# GPIO_shield.net
KiCad netlist of a schematic drawn in EAGLE
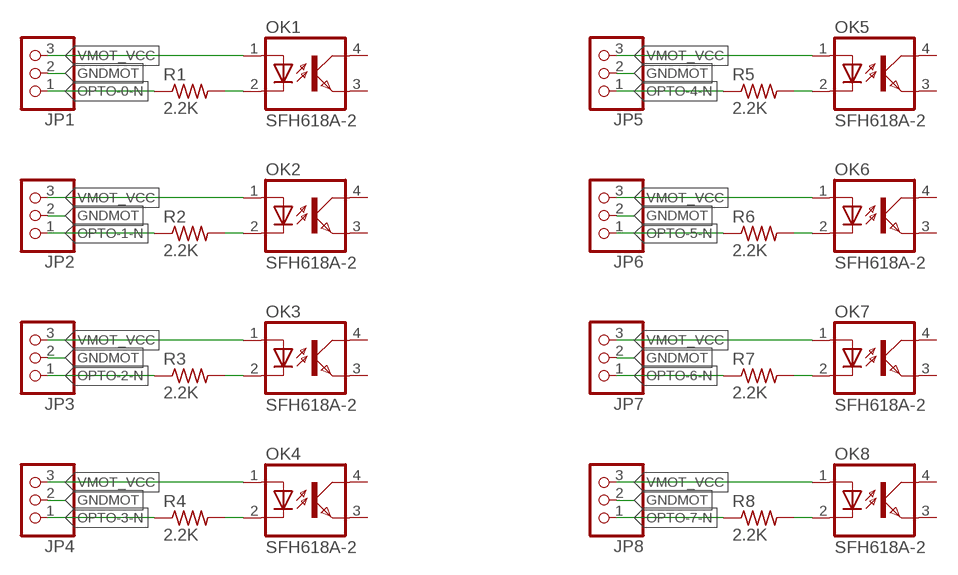
[diagram p0: schematic, sheet 1]

(export (version "E")
  (design (tool "Eeschema 10.0.6"))
  (components
    (comp (ref "JP1")
      (value "PINHD-1X3")
      (footprint "eagle-import:1X03")
      (libsource (lib "eagle-import") (part "PINHD-1X3"))
    )
    (comp (ref "JP2")
      (value "PINHD-1X3")
      (footprint "eagle-import:1X03")
      (libsource (lib "eagle-import") (part "PINHD-1X3"))
    )
    (comp (ref "JP3")
      (value "PINHD-1X3")
      (footprint "eagle-import:1X03")
      (libsource (lib "eagle-import") (part "PINHD-1X3"))
    )
    (comp (ref "JP4")
      (value "PINHD-1X3")
      (footprint "eagle-import:1X03")
      (libsource (lib "eagle-import") (part "PINHD-1X3"))
    )
    (comp (ref "JP5")
      (value "PINHD-1X3")
      (footprint "eagle-import:1X03")
      (libsource (lib "eagle-import") (part "PINHD-1X3"))
    )
    (comp (ref "JP6")
      (value "PINHD-1X3")
      (footprint "eagle-import:1X03")
      (libsource (lib "eagle-import") (part "PINHD-1X3"))
    )
    (comp (ref "JP7")
      (value "PINHD-1X3")
      (footprint "eagle-import:1X03")
      (libsource (lib "eagle-import") (part "PINHD-1X3"))
    )
    (comp (ref "JP8")
      (value "PINHD-1X3")
      (footprint "eagle-import:1X03")
      (libsource (lib "eagle-import") (part "PINHD-1X3"))
    )
    (comp (ref "OK1")
      (value "SFH618A-2")
      (footprint "eagle-import:DIP4")
      (fields (field (name "MF") "VISHAY/TELEFUNKEN"))
      (libsource (lib "eagle-import") (part "SFH618?A-2"))
    )
    (comp (ref "OK2")
      (value "SFH618A-2")
      (footprint "eagle-import:DIP4")
      (fields (field (name "MF") "VISHAY/TELEFUNKEN"))
      (libsource (lib "eagle-import") (part "SFH618?A-2"))
    )
    (comp (ref "OK3")
      (value "SFH618A-2")
      (footprint "eagle-import:DIP4")
      (fields (field (name "MF") "VISHAY/TELEFUNKEN"))
      (libsource (lib "eagle-import") (part "SFH618?A-2"))
    )
    (comp (ref "OK4")
      (value "SFH618A-2")
      (footprint "eagle-import:DIP4")
      (fields (field (name "MF") "VISHAY/TELEFUNKEN"))
      (libsource (lib "eagle-import") (part "SFH618?A-2"))
    )
    (comp (ref "OK5")
      (value "SFH618A-2")
      (footprint "eagle-import:DIP4")
      (fields (field (name "MF") "VISHAY/TELEFUNKEN"))
      (libsource (lib "eagle-import") (part "SFH618?A-2"))
    )
    (comp (ref "OK6")
      (value "SFH618A-2")
      (footprint "eagle-import:DIP4")
      (fields (field (name "MF") "VISHAY/TELEFUNKEN"))
      (libsource (lib "eagle-import") (part "SFH618?A-2"))
    )
    (comp (ref "OK7")
      (value "SFH618A-2")
      (footprint "eagle-import:DIP4")
      (fields (field (name "MF") "VISHAY/TELEFUNKEN"))
      (libsource (lib "eagle-import") (part "SFH618?A-2"))
    )
    (comp (ref "OK8")
      (value "SFH618A-2")
      (footprint "eagle-import:DIP4")
      (fields (field (name "MF") "VISHAY/TELEFUNKEN"))
      (libsource (lib "eagle-import") (part "SFH618?A-2"))
    )
    (comp (ref "R1")
      (value "2.2K")
      (footprint "eagle-import:0204V")
      (libsource (lib "eagle-import") (part "R-US_0204/2V"))
    )
    (comp (ref "R2")
      (value "2.2K")
      (footprint "eagle-import:0204V")
      (libsource (lib "eagle-import") (part "R-US_0204/2V"))
    )
    (comp (ref "R3")
      (value "2.2K")
      (footprint "eagle-import:0204V")
      (libsource (lib "eagle-import") (part "R-US_0204/2V"))
    )
    (comp (ref "R4")
      (value "2.2K")
      (footprint "eagle-import:0204V")
      (libsource (lib "eagle-import") (part "R-US_0204/2V"))
    )
    (comp (ref "R5")
      (value "2.2K")
      (footprint "eagle-import:0204V")
      (libsource (lib "eagle-import") (part "R-US_0204/2V"))
    )
    (comp (ref "R6")
      (value "2.2K")
      (footprint "eagle-import:0204V")
      (libsource (lib "eagle-import") (part "R-US_0204/2V"))
    )
    (comp (ref "R7")
      (value "2.2K")
      (footprint "eagle-import:0204V")
      (libsource (lib "eagle-import") (part "R-US_0204/2V"))
    )
    (comp (ref "R8")
      (value "2.2K")
      (footprint "eagle-import:0204V")
      (libsource (lib "eagle-import") (part "R-US_0204/2V"))
    )
  )
  (nets
    (net (code "1") (name "GNDMOT") (class "Default")
      (node (ref "JP1") (pin "2") (pinfunction "2_2") (pintype "passive"))
      (node (ref "JP2") (pin "2") (pinfunction "2_2") (pintype "passive"))
      (node (ref "JP3") (pin "2") (pinfunction "2_2") (pintype "passive"))
      (node (ref "JP4") (pin "2") (pinfunction "2_2") (pintype "passive"))
      (node (ref "JP5") (pin "2") (pinfunction "2_2") (pintype "passive"))
      (node (ref "JP6") (pin "2") (pinfunction "2_2") (pintype "passive"))
      (node (ref "JP7") (pin "2") (pinfunction "2_2") (pintype "passive"))
      (node (ref "JP8") (pin "2") (pinfunction "2_2") (pintype "passive"))
    )
    (net (code "2") (name "Net-(OK1-C)") (class "Default")
      (node (ref "OK1") (pin "2") (pinfunction "C_2") (pintype "passive"))
      (node (ref "R1") (pin "2") (pinfunction "2_2") (pintype "passive"))
    )
    (net (code "3") (name "Net-(OK2-C)") (class "Default")
      (node (ref "OK2") (pin "2") (pinfunction "C_2") (pintype "passive"))
      (node (ref "R2") (pin "2") (pinfunction "2_2") (pintype "passive"))
    )
    (net (code "4") (name "Net-(OK3-C)") (class "Default")
      (node (ref "OK3") (pin "2") (pinfunction "C_2") (pintype "passive"))
      (node (ref "R3") (pin "2") (pinfunction "2_2") (pintype "passive"))
    )
    (net (code "5") (name "Net-(OK4-C)") (class "Default")
      (node (ref "OK4") (pin "2") (pinfunction "C_2") (pintype "passive"))
      (node (ref "R4") (pin "2") (pinfunction "2_2") (pintype "passive"))
    )
    (net (code "6") (name "Net-(OK5-C)") (class "Default")
      (node (ref "OK5") (pin "2") (pinfunction "C_2") (pintype "passive"))
      (node (ref "R5") (pin "2") (pinfunction "2_2") (pintype "passive"))
    )
    (net (code "7") (name "Net-(OK6-C)") (class "Default")
      (node (ref "OK6") (pin "2") (pinfunction "C_2") (pintype "passive"))
      (node (ref "R6") (pin "2") (pinfunction "2_2") (pintype "passive"))
    )
    (net (code "8") (name "Net-(OK7-C)") (class "Default")
      (node (ref "OK7") (pin "2") (pinfunction "C_2") (pintype "passive"))
      (node (ref "R7") (pin "2") (pinfunction "2_2") (pintype "passive"))
    )
    (net (code "9") (name "Net-(OK8-C)") (class "Default")
      (node (ref "OK8") (pin "2") (pinfunction "C_2") (pintype "passive"))
      (node (ref "R8") (pin "2") (pinfunction "2_2") (pintype "passive"))
    )
    (net (code "10") (name "OPTO-0-N") (class "Default")
      (node (ref "JP1") (pin "1") (pinfunction "1_1") (pintype "passive"))
      (node (ref "R1") (pin "1") (pinfunction "1_1") (pintype "passive"))
    )
    (net (code "11") (name "OPTO-1-N") (class "Default")
      (node (ref "JP2") (pin "1") (pinfunction "1_1") (pintype "passive"))
      (node (ref "R2") (pin "1") (pinfunction "1_1") (pintype "passive"))
    )
    (net (code "12") (name "OPTO-2-N") (class "Default")
      (node (ref "JP3") (pin "1") (pinfunction "1_1") (pintype "passive"))
      (node (ref "R3") (pin "1") (pinfunction "1_1") (pintype "passive"))
    )
    (net (code "13") (name "OPTO-3-N") (class "Default")
      (node (ref "JP4") (pin "1") (pinfunction "1_1") (pintype "passive"))
      (node (ref "R4") (pin "1") (pinfunction "1_1") (pintype "passive"))
    )
    (net (code "14") (name "OPTO-4-N") (class "Default")
      (node (ref "JP5") (pin "1") (pinfunction "1_1") (pintype "passive"))
      (node (ref "R5") (pin "1") (pinfunction "1_1") (pintype "passive"))
    )
    (net (code "15") (name "OPTO-5-N") (class "Default")
      (node (ref "JP6") (pin "1") (pinfunction "1_1") (pintype "passive"))
      (node (ref "R6") (pin "1") (pinfunction "1_1") (pintype "passive"))
    )
    (net (code "16") (name "OPTO-6-N") (class "Default")
      (node (ref "JP7") (pin "1") (pinfunction "1_1") (pintype "passive"))
      (node (ref "R7") (pin "1") (pinfunction "1_1") (pintype "passive"))
    )
    (net (code "17") (name "OPTO-7-N") (class "Default")
      (node (ref "JP8") (pin "1") (pinfunction "1_1") (pintype "passive"))
      (node (ref "R8") (pin "1") (pinfunction "1_1") (pintype "passive"))
    )
    (net (code "18") (name "VMOT_VCC") (class "Default")
      (node (ref "JP1") (pin "3") (pinfunction "3_3") (pintype "passive"))
      (node (ref "JP2") (pin "3") (pinfunction "3_3") (pintype "passive"))
      (node (ref "JP3") (pin "3") (pinfunction "3_3") (pintype "passive"))
      (node (ref "JP4") (pin "3") (pinfunction "3_3") (pintype "passive"))
      (node (ref "JP5") (pin "3") (pinfunction "3_3") (pintype "passive"))
      (node (ref "JP6") (pin "3") (pinfunction "3_3") (pintype "passive"))
      (node (ref "JP7") (pin "3") (pinfunction "3_3") (pintype "passive"))
      (node (ref "JP8") (pin "3") (pinfunction "3_3") (pintype "passive"))
      (node (ref "OK1") (pin "1") (pinfunction "A_1") (pintype "passive"))
      (node (ref "OK2") (pin "1") (pinfunction "A_1") (pintype "passive"))
      (node (ref "OK3") (pin "1") (pinfunction "A_1") (pintype "passive"))
      (node (ref "OK4") (pin "1") (pinfunction "A_1") (pintype "passive"))
      (node (ref "OK5") (pin "1") (pinfunction "A_1") (pintype "passive"))
      (node (ref "OK6") (pin "1") (pinfunction "A_1") (pintype "passive"))
      (node (ref "OK7") (pin "1") (pinfunction "A_1") (pintype "passive"))
      (node (ref "OK8") (pin "1") (pinfunction "A_1") (pintype "passive"))
    )
    (net (code "19") (name "unconnected-(OK1-COL-Pad4)") (class "Default")
      (node (ref "OK1") (pin "4") (pinfunction "COL_4") (pintype "passive"))
    )
    (net (code "20") (name "unconnected-(OK1-EMIT-Pad3)") (class "Default")
      (node (ref "OK1") (pin "3") (pinfunction "EMIT_3") (pintype "passive"))
    )
    (net (code "21") (name "unconnected-(OK2-COL-Pad4)") (class "Default")
      (node (ref "OK2") (pin "4") (pinfunction "COL_4") (pintype "passive"))
    )
    (net (code "22") (name "unconnected-(OK2-EMIT-Pad3)") (class "Default")
      (node (ref "OK2") (pin "3") (pinfunction "EMIT_3") (pintype "passive"))
    )
    (net (code "23") (name "unconnected-(OK3-COL-Pad4)") (class "Default")
      (node (ref "OK3") (pin "4") (pinfunction "COL_4") (pintype "passive"))
    )
    (net (code "24") (name "unconnected-(OK3-EMIT-Pad3)") (class "Default")
      (node (ref "OK3") (pin "3") (pinfunction "EMIT_3") (pintype "passive"))
    )
    (net (code "25") (name "unconnected-(OK4-COL-Pad4)") (class "Default")
      (node (ref "OK4") (pin "4") (pinfunction "COL_4") (pintype "passive"))
    )
    (net (code "26") (name "unconnected-(OK4-EMIT-Pad3)") (class "Default")
      (node (ref "OK4") (pin "3") (pinfunction "EMIT_3") (pintype "passive"))
    )
    (net (code "27") (name "unconnected-(OK5-COL-Pad4)") (class "Default")
      (node (ref "OK5") (pin "4") (pinfunction "COL_4") (pintype "passive"))
    )
    (net (code "28") (name "unconnected-(OK5-EMIT-Pad3)") (class "Default")
      (node (ref "OK5") (pin "3") (pinfunction "EMIT_3") (pintype "passive"))
    )
    (net (code "29") (name "unconnected-(OK6-COL-Pad4)") (class "Default")
      (node (ref "OK6") (pin "4") (pinfunction "COL_4") (pintype "passive"))
    )
    (net (code "30") (name "unconnected-(OK6-EMIT-Pad3)") (class "Default")
      (node (ref "OK6") (pin "3") (pinfunction "EMIT_3") (pintype "passive"))
    )
    (net (code "31") (name "unconnected-(OK7-COL-Pad4)") (class "Default")
      (node (ref "OK7") (pin "4") (pinfunction "COL_4") (pintype "passive"))
    )
    (net (code "32") (name "unconnected-(OK7-EMIT-Pad3)") (class "Default")
      (node (ref "OK7") (pin "3") (pinfunction "EMIT_3") (pintype "passive"))
    )
    (net (code "33") (name "unconnected-(OK8-COL-Pad4)") (class "Default")
      (node (ref "OK8") (pin "4") (pinfunction "COL_4") (pintype "passive"))
    )
    (net (code "34") (name "unconnected-(OK8-EMIT-Pad3)") (class "Default")
      (node (ref "OK8") (pin "3") (pinfunction "EMIT_3") (pintype "passive"))
    )
  )
)
